# cdf-interrupter.net
KiCad netlist of a schematic drawn in EAGLE
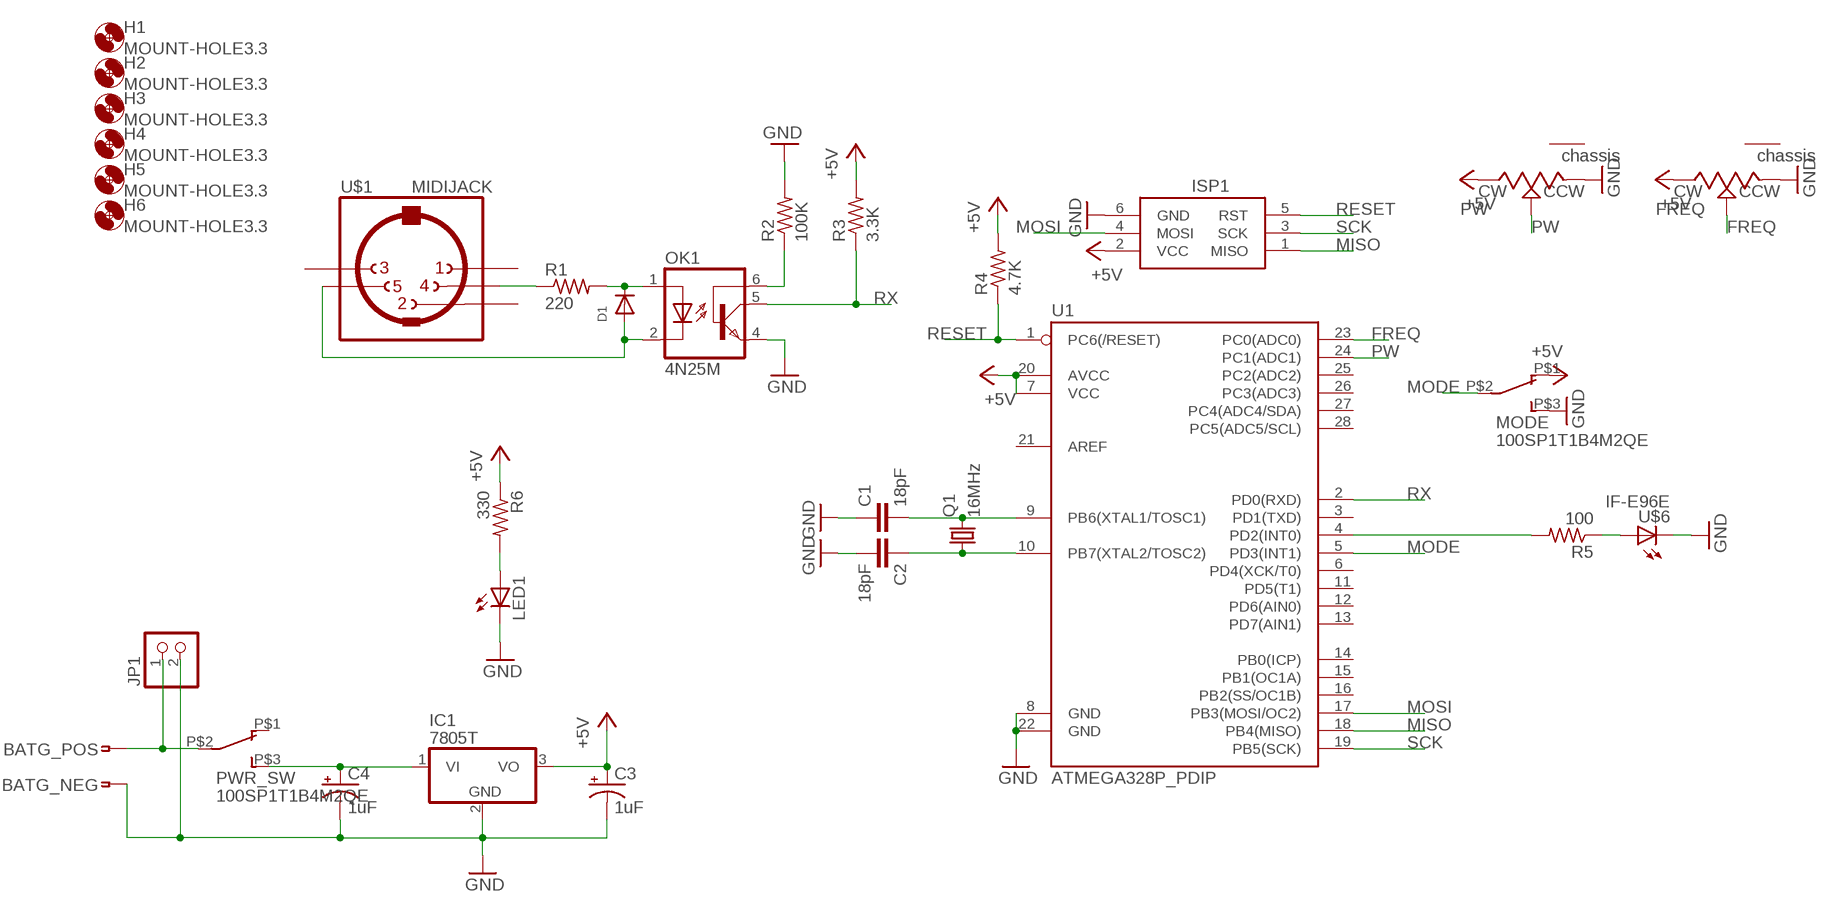
[diagram p0: schematic, sheet 1]

(export (version "E")
  (design (tool "Eeschema 10.0.6"))
  (components
    (comp (ref "BAT")
      (value "KEYSTONE-9V-BAT-HOLDER-1291")
      (footprint "eagle-import:KEYSTONE-9V-BAT-HOLDER-1291")
      (libsource (lib "eagle-import") (part "KEYSTONE-9V-BAT-HOLDER-1291"))
    )
    (comp (ref "C1")
      (value "18pF")
      (footprint "eagle-import:C050-025X075")
      (libsource (lib "eagle-import") (part "C-EU050-025X075"))
    )
    (comp (ref "C2")
      (value "18pF")
      (footprint "eagle-import:C050-025X075")
      (libsource (lib "eagle-import") (part "C-EU050-025X075"))
    )
    (comp (ref "C3")
      (value "1uF")
      (footprint "eagle-import:E2-4")
      (libsource (lib "eagle-import") (part "CPOL-USE2-4"))
    )
    (comp (ref "C4")
      (value "1uF")
      (footprint "eagle-import:E2-4")
      (libsource (lib "eagle-import") (part "CPOL-USE2-4"))
    )
    (comp (ref "D1")
      (value "DIODEDO-1N4148")
      (footprint "eagle-import:DO-1N4148")
      (libsource (lib "eagle-import") (part "DIODEDO-1N4148"))
    )
    (comp (ref "FREQ")
      (value "POTENTIOMETERPTV09A_VERTICAL")
      (footprint "eagle-import:PTV09A-4")
      (libsource (lib "eagle-import") (part "POTENTIOMETERPTV09A_VERTICAL"))
    )
    (comp (ref "H1")
      (value "MOUNT-HOLE3.3")
      (footprint "eagle-import:3,3")
      (libsource (lib "eagle-import") (part "MOUNT-HOLE3.3"))
    )
    (comp (ref "H2")
      (value "MOUNT-HOLE3.3")
      (footprint "eagle-import:3,3")
      (libsource (lib "eagle-import") (part "MOUNT-HOLE3.3"))
    )
    (comp (ref "H3")
      (value "MOUNT-HOLE3.3")
      (footprint "eagle-import:3,3")
      (libsource (lib "eagle-import") (part "MOUNT-HOLE3.3"))
    )
    (comp (ref "H4")
      (value "MOUNT-HOLE3.3")
      (footprint "eagle-import:3,3")
      (libsource (lib "eagle-import") (part "MOUNT-HOLE3.3"))
    )
    (comp (ref "H5")
      (value "MOUNT-HOLE3.3")
      (footprint "eagle-import:3,3")
      (libsource (lib "eagle-import") (part "MOUNT-HOLE3.3"))
    )
    (comp (ref "H6")
      (value "MOUNT-HOLE3.3")
      (footprint "eagle-import:3,3")
      (libsource (lib "eagle-import") (part "MOUNT-HOLE3.3"))
    )
    (comp (ref "IC1")
      (value "7805T")
      (footprint "eagle-import:TO220H")
      (libsource (lib "eagle-import") (part "78T05"))
    )
    (comp (ref "ISP1")
      (value "AVRISP-BOX")
      (footprint "eagle-import:AVRISP-BOX")
      (libsource (lib "eagle-import") (part "AVRISP-BOX"))
    )
    (comp (ref "JP1")
      (value "PINHD-1X2")
      (footprint "eagle-import:1X02")
      (libsource (lib "eagle-import") (part "PINHD-1X2"))
    )
    (comp (ref "LED1")
      (value "LED5MM")
      (footprint "eagle-import:LED5MM")
      (libsource (lib "eagle-import") (part "LED5MM"))
    )
    (comp (ref "MODE")
      (value "100SP1T1B4M2QE")
      (footprint "eagle-import:100SP1T1B4M2QE")
      (libsource (lib "eagle-import") (part "100SP1T1B4M2QE"))
    )
    (comp (ref "OK1")
      (value "4N25M")
      (footprint "eagle-import:DIL06")
      (fields (field (name "MPN") "4N25-M"))
      (libsource (lib "eagle-import") (part "4N?M25"))
    )
    (comp (ref "PW")
      (value "POTENTIOMETERPTV09A_VERTICAL")
      (footprint "eagle-import:PTV09A-4")
      (libsource (lib "eagle-import") (part "POTENTIOMETERPTV09A_VERTICAL"))
    )
    (comp (ref "PWR_SW")
      (value "100SP1T1B4M2QE")
      (footprint "eagle-import:100SP1T1B4M2QE")
      (libsource (lib "eagle-import") (part "100SP1T1B4M2QE"))
    )
    (comp (ref "Q1")
      (value "16MHz")
      (footprint "eagle-import:HC49UP")
      (libsource (lib "eagle-import") (part "CRYSTALHC49UP"))
    )
    (comp (ref "R1")
      (value "220")
      (footprint "eagle-import:0204_7")
      (libsource (lib "eagle-import") (part "R-US_0204/7"))
    )
    (comp (ref "R2")
      (value "100K")
      (footprint "eagle-import:0204_7")
      (libsource (lib "eagle-import") (part "R-US_0204/7"))
    )
    (comp (ref "R3")
      (value "3.3K")
      (footprint "eagle-import:0204_7")
      (libsource (lib "eagle-import") (part "R-US_0204/7"))
    )
    (comp (ref "R4")
      (value "4.7K")
      (footprint "eagle-import:0204_7")
      (libsource (lib "eagle-import") (part "R-US_0204/7"))
    )
    (comp (ref "R5")
      (value "100")
      (footprint "eagle-import:0204_7")
      (libsource (lib "eagle-import") (part "R-US_0204/7"))
    )
    (comp (ref "R6")
      (value "330")
      (footprint "eagle-import:0204_7")
      (libsource (lib "eagle-import") (part "R-US_0204/7"))
    )
    (comp (ref "U$1")
      (value "MIDIJACK")
      (footprint "eagle-import:CP-2350")
      (libsource (lib "eagle-import") (part "MIDIJACK"))
    )
    (comp (ref "U$6")
      (value "IF-E96E")
      (footprint "eagle-import:IF-E96E")
      (libsource (lib "eagle-import") (part "IF-E96E"))
    )
    (comp (ref "U1")
      (value "ATMEGA328P_PDIP")
      (footprint "eagle-import:DIL28-3")
      (libsource (lib "eagle-import") (part "ATMEGA328P_PDIP"))
    )
  )
  (nets
    (net (code "1") (name "+5V") (class "Default")
      (node (ref "C3") (pin "+") (pinfunction "+_+") (pintype "passive"))
      (node (ref "FREQ") (pin "3") (pinfunction "CW_3") (pintype "passive"))
      (node (ref "IC1") (pin "3") (pinfunction "VO_3") (pintype "passive"))
      (node (ref "ISP1") (pin "2") (pinfunction "VCC_2") (pintype "power_in"))
      (node (ref "MODE") (pin "P$1") (pinfunction "1_P$1") (pintype "passive"))
      (node (ref "PW") (pin "3") (pinfunction "CW_3") (pintype "passive"))
      (node (ref "R3") (pin "2") (pinfunction "2_2") (pintype "passive"))
      (node (ref "R4") (pin "2") (pinfunction "2_2") (pintype "passive"))
      (node (ref "R6") (pin "1") (pinfunction "1_1") (pintype "passive"))
      (node (ref "U1") (pin "20") (pinfunction "AVCC_20") (pintype "bidirectional"))
      (node (ref "U1") (pin "7") (pinfunction "VCC_7") (pintype "bidirectional"))
    )
    (net (code "2") (name "/FREQ") (class "Default")
      (node (ref "FREQ") (pin "2") (pinfunction "WIPER_2") (pintype "passive"))
      (node (ref "U1") (pin "23") (pinfunction "PC0(ADC0)_23") (pintype "bidirectional"))
    )
    (net (code "3") (name "/MISO") (class "Default")
      (node (ref "ISP1") (pin "1") (pinfunction "MISO_1") (pintype "input"))
      (node (ref "U1") (pin "18") (pinfunction "PB4(MISO)_18") (pintype "bidirectional"))
    )
    (net (code "4") (name "/MODE") (class "Default")
      (node (ref "MODE") (pin "P$2") (pinfunction "2_P$2") (pintype "passive"))
      (node (ref "U1") (pin "5") (pinfunction "PD3(INT1)_5") (pintype "bidirectional"))
    )
    (net (code "5") (name "/MOSI") (class "Default")
      (node (ref "ISP1") (pin "4") (pinfunction "MOSI_4") (pintype "output"))
      (node (ref "U1") (pin "17") (pinfunction "PB3(MOSI/OC2)_17") (pintype "bidirectional"))
    )
    (net (code "6") (name "/PW") (class "Default")
      (node (ref "PW") (pin "2") (pinfunction "WIPER_2") (pintype "passive"))
      (node (ref "U1") (pin "24") (pinfunction "PC1(ADC1)_24") (pintype "bidirectional"))
    )
    (net (code "7") (name "/RESET") (class "Default")
      (node (ref "ISP1") (pin "5") (pinfunction "RST_5") (pintype "output"))
      (node (ref "R4") (pin "1") (pinfunction "1_1") (pintype "passive"))
      (node (ref "U1") (pin "1") (pinfunction "PC6(/RESET)_1") (pintype "bidirectional"))
    )
    (net (code "8") (name "/RX") (class "Default")
      (node (ref "OK1") (pin "5") (pinfunction "COL_5") (pintype "passive"))
      (node (ref "R3") (pin "1") (pinfunction "1_1") (pintype "passive"))
      (node (ref "U1") (pin "2") (pinfunction "PD0(RXD)_2") (pintype "bidirectional"))
    )
    (net (code "9") (name "/SCK") (class "Default")
      (node (ref "ISP1") (pin "3") (pinfunction "SCK_3") (pintype "output"))
      (node (ref "U1") (pin "19") (pinfunction "PB5(SCK)_19") (pintype "bidirectional"))
    )
    (net (code "10") (name "GND") (class "Default")
      (node (ref "BAT") (pin "P_NEG") (pinfunction "1_P_NEG") (pintype "passive"))
      (node (ref "C1") (pin "1") (pinfunction "1_1") (pintype "passive"))
      (node (ref "C2") (pin "2") (pinfunction "2_2") (pintype "passive"))
      (node (ref "C3") (pin "-") (pinfunction "-_-") (pintype "passive"))
      (node (ref "C4") (pin "-") (pinfunction "-_-") (pintype "passive"))
      (node (ref "FREQ") (pin "1") (pinfunction "CCW_1") (pintype "passive"))
      (node (ref "IC1") (pin "2") (pinfunction "GND_2") (pintype "passive"))
      (node (ref "ISP1") (pin "6") (pinfunction "GND_6") (pintype "power_in"))
      (node (ref "JP1") (pin "2") (pinfunction "2_2") (pintype "passive"))
      (node (ref "LED1") (pin "K") (pinfunction "C_K") (pintype "passive"))
      (node (ref "MODE") (pin "P$3") (pinfunction "3_P$3") (pintype "passive"))
      (node (ref "OK1") (pin "4") (pinfunction "EMI_4") (pintype "passive"))
      (node (ref "PW") (pin "1") (pinfunction "CCW_1") (pintype "passive"))
      (node (ref "R2") (pin "2") (pinfunction "2_2") (pintype "passive"))
      (node (ref "U$6") (pin "P$1_CATHODE-") (pinfunction "C_P$1_CATHODE-") (pintype "passive"))
      (node (ref "U1") (pin "22") (pinfunction "GND_22") (pintype "bidirectional"))
      (node (ref "U1") (pin "8") (pinfunction "GND_8") (pintype "bidirectional"))
    )
    (net (code "11") (name "Net-(BATB-1)") (class "Default")
      (node (ref "BAT") (pin "P_POS") (pinfunction "1_P_POS") (pintype "passive"))
      (node (ref "JP1") (pin "1") (pinfunction "1_1") (pintype "passive"))
      (node (ref "PWR_SW") (pin "P$2") (pinfunction "2_P$2") (pintype "passive"))
    )
    (net (code "12") (name "Net-(IC1-VI)") (class "Default")
      (node (ref "C4") (pin "+") (pinfunction "+_+") (pintype "passive"))
      (node (ref "IC1") (pin "1") (pinfunction "VI_1") (pintype "input"))
      (node (ref "PWR_SW") (pin "P$3") (pinfunction "3_P$3") (pintype "passive"))
    )
    (net (code "13") (name "Net-(LED1-PadA)") (class "Default")
      (node (ref "LED1") (pin "A") (pinfunction "A_A") (pintype "passive"))
      (node (ref "R6") (pin "2") (pinfunction "2_2") (pintype "passive"))
    )
    (net (code "14") (name "Net-(OK1-A)") (class "Default")
      (node (ref "D1") (pin "C") (pinfunction "C_C") (pintype "passive"))
      (node (ref "OK1") (pin "1") (pinfunction "A_1") (pintype "passive"))
      (node (ref "R1") (pin "2") (pinfunction "2_2") (pintype "passive"))
    )
    (net (code "15") (name "Net-(OK1-BAS)") (class "Default")
      (node (ref "OK1") (pin "6") (pinfunction "BAS_6") (pintype "passive"))
      (node (ref "R2") (pin "1") (pinfunction "1_1") (pintype "passive"))
    )
    (net (code "16") (name "Net-(OK1-C)") (class "Default")
      (node (ref "D1") (pin "A") (pinfunction "A_A") (pintype "passive"))
      (node (ref "OK1") (pin "2") (pinfunction "C_2") (pintype "passive"))
      (node (ref "U$1") (pin "5") (pinfunction "5_5") (pintype "passive"))
    )
    (net (code "17") (name "Net-(R1-Pad1)") (class "Default")
      (node (ref "R1") (pin "1") (pinfunction "1_1") (pintype "passive"))
      (node (ref "U$1") (pin "4") (pinfunction "4_4") (pintype "passive"))
    )
    (net (code "18") (name "Net-(U$6-A)") (class "Default")
      (node (ref "R5") (pin "1") (pinfunction "1_1") (pintype "passive"))
      (node (ref "U$6") (pin "P$2_ANODE+") (pinfunction "A_P$2_ANODE+") (pintype "passive"))
    )
    (net (code "19") (name "Net-(U1-PB6(XTAL1{slash}TOSC1))") (class "Default")
      (node (ref "C1") (pin "2") (pinfunction "2_2") (pintype "passive"))
      (node (ref "Q1") (pin "2") (pinfunction "2_2") (pintype "passive"))
      (node (ref "U1") (pin "9") (pinfunction "PB6(XTAL1/TOSC1)_9") (pintype "bidirectional"))
    )
    (net (code "20") (name "Net-(U1-PB7(XTAL2{slash}TOSC2))") (class "Default")
      (node (ref "C2") (pin "1") (pinfunction "1_1") (pintype "passive"))
      (node (ref "Q1") (pin "1") (pinfunction "1_1") (pintype "passive"))
      (node (ref "U1") (pin "10") (pinfunction "PB7(XTAL2/TOSC2)_10") (pintype "bidirectional"))
    )
    (net (code "21") (name "Net-(U1-PD2(INT0))") (class "Default")
      (node (ref "R5") (pin "2") (pinfunction "2_2") (pintype "passive"))
      (node (ref "U1") (pin "4") (pinfunction "PD2(INT0)_4") (pintype "bidirectional"))
    )
    (net (code "22") (name "unconnected-(FREQ-CHASSIS-Pad4)") (class "Default")
      (node (ref "FREQ") (pin "4") (pinfunction "CHASSIS_4") (pintype "passive"))
    )
    (net (code "23") (name "unconnected-(PW-CHASSIS-Pad4)") (class "Default")
      (node (ref "PW") (pin "4") (pinfunction "CHASSIS_4") (pintype "passive"))
    )
    (net (code "24") (name "unconnected-(PWR_SW-1-PadP$1)") (class "Default")
      (node (ref "PWR_SW") (pin "P$1") (pinfunction "1_P$1") (pintype "passive"))
    )
    (net (code "25") (name "unconnected-(U$1-Pad1)") (class "Default")
      (node (ref "U$1") (pin "1") (pinfunction "1_1") (pintype "passive"))
    )
    (net (code "26") (name "unconnected-(U$1-Pad2)") (class "Default")
      (node (ref "U$1") (pin "2") (pinfunction "2_2") (pintype "passive"))
    )
    (net (code "27") (name "unconnected-(U$1-Pad3)") (class "Default")
      (node (ref "U$1") (pin "3") (pinfunction "3_3") (pintype "passive"))
    )
    (net (code "28") (name "unconnected-(U1-AREF-Pad21)") (class "Default")
      (node (ref "U1") (pin "21") (pinfunction "AREF_21") (pintype "bidirectional"))
    )
    (net (code "29") (name "unconnected-(U1-PB0(ICP)-Pad14)") (class "Default")
      (node (ref "U1") (pin "14") (pinfunction "PB0(ICP)_14") (pintype "bidirectional"))
    )
    (net (code "30") (name "unconnected-(U1-PB1(OC1A)-Pad15)") (class "Default")
      (node (ref "U1") (pin "15") (pinfunction "PB1(OC1A)_15") (pintype "bidirectional"))
    )
    (net (code "31") (name "unconnected-(U1-PB2(SS{slash}OC1B)-Pad16)") (class "Default")
      (node (ref "U1") (pin "16") (pinfunction "PB2(SS/OC1B)_16") (pintype "bidirectional"))
    )
    (net (code "32") (name "unconnected-(U1-PC2(ADC2)-Pad25)") (class "Default")
      (node (ref "U1") (pin "25") (pinfunction "PC2(ADC2)_25") (pintype "bidirectional"))
    )
    (net (code "33") (name "unconnected-(U1-PC3(ADC3)-Pad26)") (class "Default")
      (node (ref "U1") (pin "26") (pinfunction "PC3(ADC3)_26") (pintype "bidirectional"))
    )
    (net (code "34") (name "unconnected-(U1-PC4(ADC4{slash}SDA)-Pad27)") (class "Default")
      (node (ref "U1") (pin "27") (pinfunction "PC4(ADC4/SDA)_27") (pintype "bidirectional"))
    )
    (net (code "35") (name "unconnected-(U1-PC5(ADC5{slash}SCL)-Pad28)") (class "Default")
      (node (ref "U1") (pin "28") (pinfunction "PC5(ADC5/SCL)_28") (pintype "bidirectional"))
    )
    (net (code "36") (name "unconnected-(U1-PD1(TXD)-Pad3)") (class "Default")
      (node (ref "U1") (pin "3") (pinfunction "PD1(TXD)_3") (pintype "bidirectional"))
    )
    (net (code "37") (name "unconnected-(U1-PD4(XCK{slash}T0)-Pad6)") (class "Default")
      (node (ref "U1") (pin "6") (pinfunction "PD4(XCK/T0)_6") (pintype "bidirectional"))
    )
    (net (code "38") (name "unconnected-(U1-PD5(T1)-Pad11)") (class "Default")
      (node (ref "U1") (pin "11") (pinfunction "PD5(T1)_11") (pintype "bidirectional"))
    )
    (net (code "39") (name "unconnected-(U1-PD6(AIN0)-Pad12)") (class "Default")
      (node (ref "U1") (pin "12") (pinfunction "PD6(AIN0)_12") (pintype "bidirectional"))
    )
    (net (code "40") (name "unconnected-(U1-PD7(AIN1)-Pad13)") (class "Default")
      (node (ref "U1") (pin "13") (pinfunction "PD7(AIN1)_13") (pintype "bidirectional"))
    )
  )
)
